# 3x3_v2.net
KiCad netlist of a schematic drawn in Altium Designer
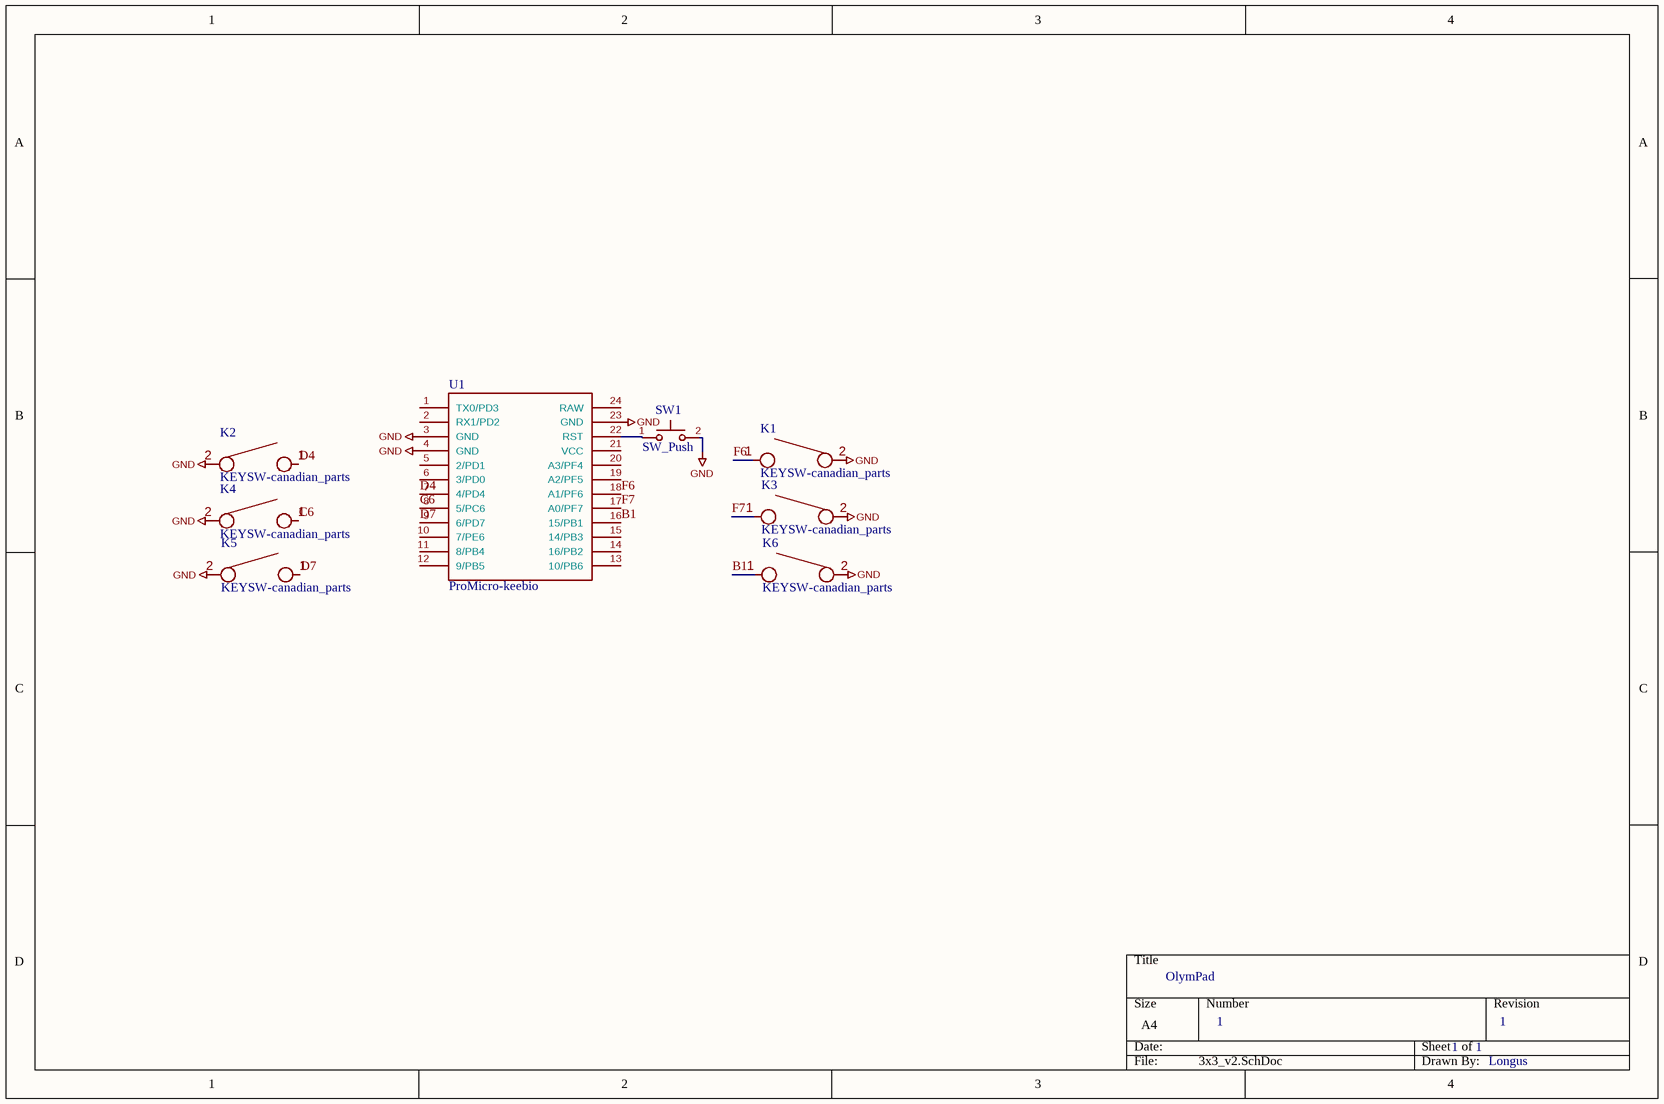
[diagram p0: 3x3_v2.SchDoc]

(export (version "E")
  (design (tool "Eeschema 10.0.6"))
  (components
    (comp (ref "K1")
      (value "KEYSW-canadian_parts")
      (footprint "Socket")
      (libsource (lib "Macropad") (part "KEYSW-canadian_parts"))
    )
    (comp (ref "K2")
      (value "KEYSW-canadian_parts")
      (footprint "Socket")
      (libsource (lib "Macropad") (part "KEYSW-canadian_parts"))
    )
    (comp (ref "K3")
      (value "KEYSW-canadian_parts")
      (footprint "Socket")
      (libsource (lib "Macropad") (part "KEYSW-canadian_parts"))
    )
    (comp (ref "K4")
      (value "KEYSW-canadian_parts")
      (footprint "Socket")
      (libsource (lib "Macropad") (part "KEYSW-canadian_parts"))
    )
    (comp (ref "K5")
      (value "KEYSW-canadian_parts")
      (footprint "Socket")
      (libsource (lib "Macropad") (part "KEYSW-canadian_parts"))
    )
    (comp (ref "K6")
      (value "KEYSW-canadian_parts")
      (footprint "Socket")
      (libsource (lib "Macropad") (part "KEYSW-canadian_parts"))
    )
    (comp (ref "SW1") (value "SW_Push") (footprint "Reset") (libsource (lib "Macropad") (part "SW_Push")))
    (comp (ref "U1")
      (value "ProMicro-keebio")
      (footprint "Pro-Micro")
      (libsource (lib "Macropad") (part "ProMicro-keebio"))
    )
  )
  (nets
    (net (code "1") (name "/B1") (class "Default")
      (node (ref "K6") (pin "1") (pinfunction "1_1") (pintype "passive"))
      (node (ref "U1") (pin "16") (pinfunction "15/PB1_16") (pintype "passive"))
    )
    (net (code "2") (name "/C6") (class "Default")
      (node (ref "K4") (pin "1") (pinfunction "1_1") (pintype "passive"))
      (node (ref "U1") (pin "8") (pinfunction "5/PC6_8") (pintype "passive"))
    )
    (net (code "3") (name "/D4") (class "Default")
      (node (ref "K2") (pin "1") (pinfunction "1_1") (pintype "passive"))
      (node (ref "U1") (pin "7") (pinfunction "4/PD4_7") (pintype "passive"))
    )
    (net (code "4") (name "/D7") (class "Default")
      (node (ref "K5") (pin "1") (pinfunction "1_1") (pintype "passive"))
      (node (ref "U1") (pin "9") (pinfunction "6/PD7_9") (pintype "passive"))
    )
    (net (code "5") (name "/F6") (class "Default")
      (node (ref "K1") (pin "1") (pinfunction "1_1") (pintype "passive"))
      (node (ref "U1") (pin "18") (pinfunction "A1/PF6_18") (pintype "passive"))
    )
    (net (code "6") (name "/F7") (class "Default")
      (node (ref "K3") (pin "1") (pinfunction "1_1") (pintype "passive"))
      (node (ref "U1") (pin "17") (pinfunction "A0/PF7_17") (pintype "passive"))
    )
    (net (code "7") (name "GND") (class "Default")
      (node (ref "K1") (pin "2") (pinfunction "2_2") (pintype "passive"))
      (node (ref "K2") (pin "2") (pinfunction "2_2") (pintype "passive"))
      (node (ref "K3") (pin "2") (pinfunction "2_2") (pintype "passive"))
      (node (ref "K4") (pin "2") (pinfunction "2_2") (pintype "passive"))
      (node (ref "K5") (pin "2") (pinfunction "2_2") (pintype "passive"))
      (node (ref "K6") (pin "2") (pinfunction "2_2") (pintype "passive"))
      (node (ref "SW1") (pin "2") (pinfunction "2_2") (pintype "passive"))
      (node (ref "U1") (pin "23") (pinfunction "GND_23") (pintype "passive"))
      (node (ref "U1") (pin "3") (pinfunction "GND_3") (pintype "passive"))
      (node (ref "U1") (pin "4") (pinfunction "GND_4") (pintype "passive"))
    )
    (net (code "8") (name "Net-(U1-RST)") (class "Default")
      (node (ref "SW1") (pin "1") (pinfunction "1_1") (pintype "passive"))
      (node (ref "U1") (pin "22") (pinfunction "RST_22") (pintype "passive"))
    )
    (net (code "9") (name "unconnected-(U1-2{slash}PD1-Pad5)") (class "Default")
      (node (ref "U1") (pin "5") (pinfunction "2/PD1_5") (pintype "passive"))
    )
    (net (code "10") (name "unconnected-(U1-3{slash}PD0-Pad6)") (class "Default")
      (node (ref "U1") (pin "6") (pinfunction "3/PD0_6") (pintype "passive"))
    )
    (net (code "11") (name "unconnected-(U1-7{slash}PE6-Pad10)") (class "Default")
      (node (ref "U1") (pin "10") (pinfunction "7/PE6_10") (pintype "passive"))
    )
    (net (code "12") (name "unconnected-(U1-8{slash}PB4-Pad11)") (class "Default")
      (node (ref "U1") (pin "11") (pinfunction "8/PB4_11") (pintype "passive"))
    )
    (net (code "13") (name "unconnected-(U1-9{slash}PB5-Pad12)") (class "Default")
      (node (ref "U1") (pin "12") (pinfunction "9/PB5_12") (pintype "passive"))
    )
    (net (code "14") (name "unconnected-(U1-10{slash}PB6-Pad13)") (class "Default")
      (node (ref "U1") (pin "13") (pinfunction "10/PB6_13") (pintype "passive"))
    )
    (net (code "15") (name "unconnected-(U1-14{slash}PB3-Pad15)") (class "Default")
      (node (ref "U1") (pin "15") (pinfunction "14/PB3_15") (pintype "passive"))
    )
    (net (code "16") (name "unconnected-(U1-16{slash}PB2-Pad14)") (class "Default")
      (node (ref "U1") (pin "14") (pinfunction "16/PB2_14") (pintype "passive"))
    )
    (net (code "17") (name "unconnected-(U1-A2{slash}PF5-Pad19)") (class "Default")
      (node (ref "U1") (pin "19") (pinfunction "A2/PF5_19") (pintype "passive"))
    )
    (net (code "18") (name "unconnected-(U1-A3{slash}PF4-Pad20)") (class "Default")
      (node (ref "U1") (pin "20") (pinfunction "A3/PF4_20") (pintype "passive"))
    )
    (net (code "19") (name "unconnected-(U1-RAW-Pad24)") (class "Default")
      (node (ref "U1") (pin "24") (pinfunction "RAW_24") (pintype "passive"))
    )
    (net (code "20") (name "unconnected-(U1-RX1{slash}PD2-Pad2)") (class "Default")
      (node (ref "U1") (pin "2") (pinfunction "RX1/PD2_2") (pintype "passive"))
    )
    (net (code "21") (name "unconnected-(U1-TX0{slash}PD3-Pad1)") (class "Default")
      (node (ref "U1") (pin "1") (pinfunction "TX0/PD3_1") (pintype "passive"))
    )
    (net (code "22") (name "unconnected-(U1-VCC-Pad21)") (class "Default")
      (node (ref "U1") (pin "21") (pinfunction "VCC_21") (pintype "passive"))
    )
  )
)
